# HDMI_CONNECTOR.net
KiCad netlist of a schematic drawn in Altium Designer
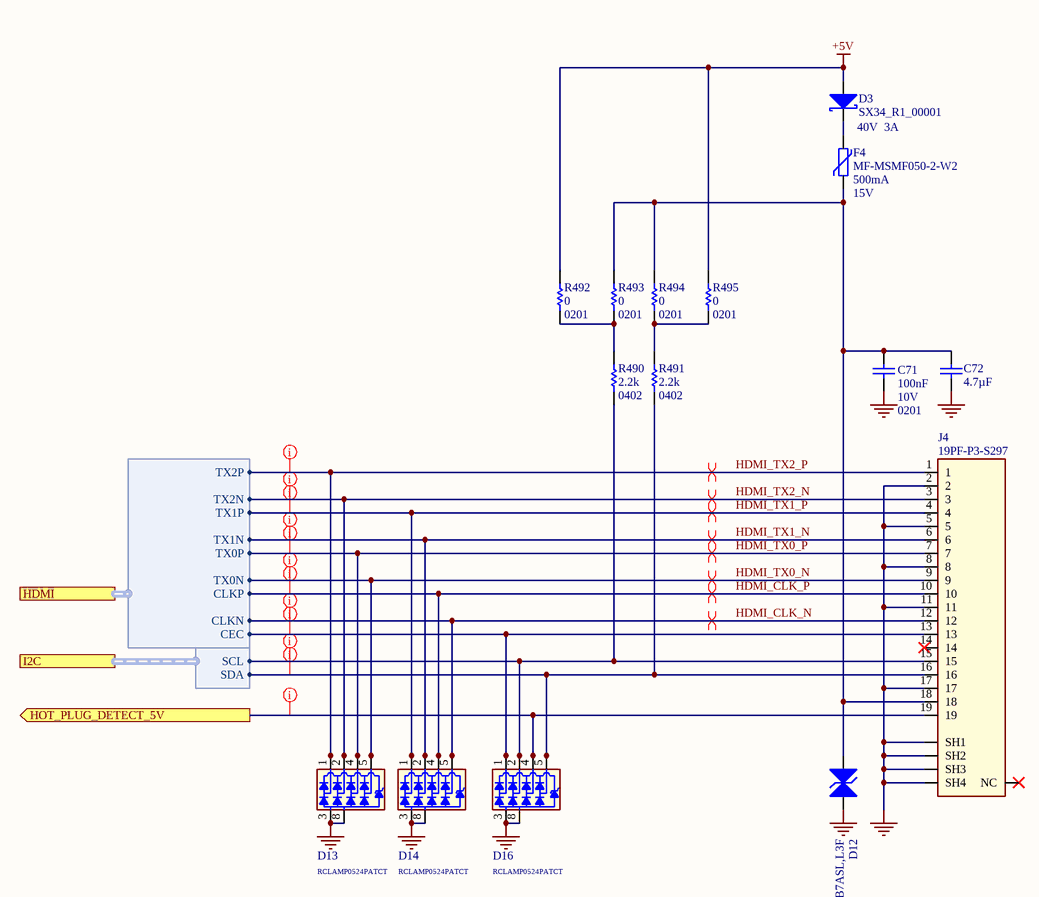
[diagram p0: HDMI_CONNECTOR.SchDoc]

(export (version "E")
  (design (tool "Eeschema 10.0.6"))
  (components
    (comp (ref "C71")
      (value "100nF")
      (footprint "CAP-0201")
      (description "CAP CHIP 0201 100nF 10% 10V X5R")
      (fields
        (field (name "PART NUMBER") "CL03A104KP3NNNC")
        (field (name "MANUFACTURER") "Samsung Electro-Mechanics")
        (field (name "VOLTAGE") "10V")
        (field (name "CASE CODE (IMPERIAL)") "0201")
      )
      (libsource (lib "Clean") (part "CAP"))
    )
    (comp (ref "C72")
      (value "4.7µF")
      (footprint "CAP-0402")
      (description "CAP CHIP 0402 4.7uF 20% 6V3 X5R")
      (fields (field (name "MANUFACTURER") "Hottech") (field (name "PART NUMBER") "C1005A475M6R3NT"))
      (libsource (lib "Clean") (part "CAP"))
    )
    (comp (ref "D3")
      (value "SX34_R1_00001")
      (footprint "SMA DO214AC")
      (description "DIODE SCHOTTKY SMD 3A 40V SMA DO214AC")
      (fields
        (field (name "PART NUMBER") "SX34-AU_R1_000A1")
        (field (name "MANUFACTURER") "Panjit")
        (field (name "MAX REVERSE VOLTAGE (DC)") "40V")
        (field (name "FORWARD CURRENT") "3A")
      )
      (libsource (lib "Clean") (part "Diode Schottky"))
    )
    (comp (ref "D12")
      (value "DF2B7ASL,L3F")
      (footprint "DF2B7ASL,L3F")
      (description "TVS BIDIRECTIONAL SMD Vr 5.5V, Vbr min 5.8V, 0.62x0.32mm")
      (fields (field (name "MANUFACTURER") "TOSHIBA"))
      (libsource (lib "Clean") (part "Diode TVS"))
    )
    (comp (ref "D13")
      (value "RCLAMP0524PATCT")
      (footprint "SLP2510P8")
      (description "TVS UNIDIRECTIONAL 4CH 0.8pF 5V SLP2510P8 10-pin 2.5x1.0x0.58mm")
      (fields (field (name "MANUFACTURER") "SEMTECH"))
      (libsource (lib "Clean") (part "RCLAMP0524PATCT"))
    )
    (comp (ref "D14")
      (value "RCLAMP0524PATCT")
      (footprint "SLP2510P8")
      (description "TVS UNIDIRECTIONAL 4CH 0.8pF 5V SLP2510P8 10-pin 2.5x1.0x0.58mm")
      (fields (field (name "MANUFACTURER") "SEMTECH"))
      (libsource (lib "Clean") (part "RCLAMP0524PATCT"))
    )
    (comp (ref "D16")
      (value "RCLAMP0524PATCT")
      (footprint "SLP2510P8")
      (description "TVS UNIDIRECTIONAL 4CH 0.8pF 5V SLP2510P8 10-pin 2.5x1.0x0.58mm")
      (fields (field (name "MANUFACTURER") "SEMTECH"))
      (libsource (lib "Clean") (part "RCLAMP0524PATCT"))
    )
    (comp (ref "F4")
      (value "MF-MSMF050-2-W2")
      (footprint "1812")
      (description "PTC RESET FUSE 15V 500MA 1812 LOGO OO ARDUINO")
      (fields
        (field (name "HOLD CURRENT") "500mA")
        (field (name "OPERATING SUPPLY VOLTAGE") "15V")
        (field (name "MANUFACTURER") "Bourns")
      )
      (libsource (lib "Clean") (part "Symbol"))
    )
    (comp (ref "J4")
      (value "19PF-P3-S297")
      (footprint "19PF-P3-S297")
      (description "CONN HDMI RIGHT ANGLE FEMALE 19 POSITIONS 7.75x23.06x16.4mm signals pins lengths 2.3mm")
      (fields (field (name "MANUFACTURER") "Contact technology"))
      (libsource (lib "Clean") (part "19PF-P3-S297"))
    )
    (comp (ref "R490")
      (value "2.2k")
      (footprint "RES-0402")
      (description "RES CHIP 0402 2k2 1% 1/16W")
      (fields
        (field (name "CASE CODE (IMPERIAL)") "0402")
        (field (name "POWER") "62.5mW")
        (field (name "TOLERANCE") "1%")
      )
      (libsource (lib "Clean") (part "RES"))
    )
    (comp (ref "R491")
      (value "2.2k")
      (footprint "RES-0402")
      (description "RES CHIP 0402 2k2 1% 1/16W")
      (fields
        (field (name "CASE CODE (IMPERIAL)") "0402")
        (field (name "POWER") "62.5mW")
        (field (name "TOLERANCE") "1%")
      )
      (libsource (lib "Clean") (part "RES"))
    )
    (comp (ref "R492")
      (value "0")
      (footprint "RES-0201")
      (description "RES CHIP 0201 0R")
      (fields
        (field (name "MANUFACTURER") "Vishay")
        (field (name "CASE CODE (IMPERIAL)") "0201")
        (field (name "PART NUMBER") "CRCW02010000Z0ED")
      )
      (libsource (lib "Clean") (part "RES"))
    )
    (comp (ref "R493")
      (value "0")
      (footprint "RES-0201")
      (description "RES CHIP 0201 0R")
      (fields
        (field (name "MANUFACTURER") "Vishay")
        (field (name "CASE CODE (IMPERIAL)") "0201")
        (field (name "PART NUMBER") "CRCW02010000Z0ED")
      )
      (libsource (lib "Clean") (part "RES"))
    )
    (comp (ref "R494")
      (value "0")
      (footprint "RES-0201")
      (description "RES CHIP 0201 0R")
      (fields
        (field (name "MANUFACTURER") "Vishay")
        (field (name "CASE CODE (IMPERIAL)") "0201")
        (field (name "PART NUMBER") "CRCW02010000Z0ED")
      )
      (libsource (lib "Clean") (part "RES"))
    )
    (comp (ref "R495")
      (value "0")
      (footprint "RES-0201")
      (description "RES CHIP 0201 0R")
      (fields
        (field (name "MANUFACTURER") "Vishay")
        (field (name "CASE CODE (IMPERIAL)") "0201")
        (field (name "PART NUMBER") "CRCW02010000Z0ED")
      )
      (libsource (lib "Clean") (part "RES"))
    )
  )
  (nets
    (net (code "3") (name "+5V") (class "Default")
      (node (ref "D3") (pin "A") (pinfunction "A_A") (pintype "passive"))
      (node (ref "R492") (pin "2") (pinfunction "2_2") (pintype "passive"))
      (node (ref "R495") (pin "2") (pinfunction "2_2") (pintype "passive"))
    )
    (net (code "4") (name "/HDMI_CLK_N") (class "Default")
      (node (ref "D14") (pin "5") (pinfunction "5_5") (pintype "passive"))
      (node (ref "D14") (pin "6") (pinfunction "6_6") (pintype "passive"))
      (node (ref "J4") (pin "12") (pinfunction "12_12") (pintype "passive"))
    )
    (net (code "5") (name "/HDMI_CLK_P") (class "Default")
      (node (ref "D14") (pin "4") (pinfunction "4_4") (pintype "passive"))
      (node (ref "D14") (pin "7") (pinfunction "7_7") (pintype "passive"))
      (node (ref "J4") (pin "10") (pinfunction "10_10") (pintype "passive"))
    )
    (net (code "6") (name "/HDMI_TX0_N") (class "Default")
      (node (ref "D13") (pin "5") (pinfunction "5_5") (pintype "passive"))
      (node (ref "D13") (pin "6") (pinfunction "6_6") (pintype "passive"))
      (node (ref "J4") (pin "9") (pinfunction "9_9") (pintype "passive"))
    )
    (net (code "7") (name "/HDMI_TX0_P") (class "Default")
      (node (ref "D13") (pin "4") (pinfunction "4_4") (pintype "passive"))
      (node (ref "D13") (pin "7") (pinfunction "7_7") (pintype "passive"))
      (node (ref "J4") (pin "7") (pinfunction "7_7") (pintype "passive"))
    )
    (net (code "8") (name "/HDMI_TX1_N") (class "Default")
      (node (ref "D14") (pin "2") (pinfunction "2_2") (pintype "passive"))
      (node (ref "D14") (pin "9") (pinfunction "9_9") (pintype "passive"))
      (node (ref "J4") (pin "6") (pinfunction "6_6") (pintype "passive"))
    )
    (net (code "9") (name "/HDMI_TX1_P") (class "Default")
      (node (ref "D14") (pin "1") (pinfunction "1_1") (pintype "passive"))
      (node (ref "D14") (pin "10") (pinfunction "10_10") (pintype "passive"))
      (node (ref "J4") (pin "4") (pinfunction "4_4") (pintype "passive"))
    )
    (net (code "10") (name "/HDMI_TX2_N") (class "Default")
      (node (ref "D13") (pin "2") (pinfunction "2_2") (pintype "passive"))
      (node (ref "D13") (pin "9") (pinfunction "9_9") (pintype "passive"))
      (node (ref "J4") (pin "3") (pinfunction "3_3") (pintype "passive"))
    )
    (net (code "11") (name "/HDMI_TX2_P") (class "Default")
      (node (ref "D13") (pin "1") (pinfunction "1_1") (pintype "passive"))
      (node (ref "D13") (pin "10") (pinfunction "10_10") (pintype "passive"))
      (node (ref "J4") (pin "1") (pinfunction "1_1") (pintype "passive"))
    )
    (net (code "13") (name "/HOT_PLUG_DETECT_5V") (class "Default")
      (node (ref "D16") (pin "4") (pinfunction "4_4") (pintype "passive"))
      (node (ref "D16") (pin "7") (pinfunction "7_7") (pintype "passive"))
      (node (ref "J4") (pin "19") (pinfunction "19_19") (pintype "passive"))
    )
    (net (code "15") (name "GND") (class "Default")
      (node (ref "C71") (pin "1") (pinfunction "1_1") (pintype "passive"))
      (node (ref "C72") (pin "1") (pinfunction "1_1") (pintype "passive"))
      (node (ref "D12") (pin "1") (pinfunction "A1_1") (pintype "passive"))
      (node (ref "D13") (pin "3") (pinfunction "3_3") (pintype "passive"))
      (node (ref "D13") (pin "8") (pinfunction "8_8") (pintype "passive"))
      (node (ref "D14") (pin "3") (pinfunction "3_3") (pintype "passive"))
      (node (ref "D14") (pin "8") (pinfunction "8_8") (pintype "passive"))
      (node (ref "D16") (pin "3") (pinfunction "3_3") (pintype "passive"))
      (node (ref "D16") (pin "8") (pinfunction "8_8") (pintype "passive"))
      (node (ref "J4") (pin "11") (pinfunction "11_11") (pintype "passive"))
      (node (ref "J4") (pin "17") (pinfunction "17_17") (pintype "passive"))
      (node (ref "J4") (pin "2") (pinfunction "2_2") (pintype "passive"))
      (node (ref "J4") (pin "5") (pinfunction "5_5") (pintype "passive"))
      (node (ref "J4") (pin "8") (pinfunction "8_8") (pintype "passive"))
      (node (ref "J4") (pin "SH1") (pinfunction "SH1_SH1") (pintype "passive"))
      (node (ref "J4") (pin "SH2") (pinfunction "SH2_SH2") (pintype "passive"))
      (node (ref "J4") (pin "SH3") (pinfunction "SH3_SH3") (pintype "passive"))
      (node (ref "J4") (pin "SH4") (pinfunction "SH4_SH4") (pintype "passive"))
    )
    (net (code "16") (name "Net-(D3-PadC)") (class "Default")
      (node (ref "D3") (pin "C") (pinfunction "C_C") (pintype "passive"))
      (node (ref "F4") (pin "2") (pinfunction "2_2") (pintype "passive"))
    )
    (net (code "17") (name "Net-(D12-A2)") (class "Default")
      (node (ref "C71") (pin "2") (pinfunction "2_2") (pintype "passive"))
      (node (ref "C72") (pin "2") (pinfunction "2_2") (pintype "passive"))
      (node (ref "D12") (pin "2") (pinfunction "A2_2") (pintype "passive"))
      (node (ref "F4") (pin "1") (pinfunction "1_1") (pintype "passive"))
      (node (ref "J4") (pin "18") (pinfunction "18_18") (pintype "passive"))
      (node (ref "R493") (pin "2") (pinfunction "2_2") (pintype "passive"))
      (node (ref "R494") (pin "2") (pinfunction "2_2") (pintype "passive"))
    )
    (net (code "18") (name "Net-(D16-Pad1)") (class "Default")
      (node (ref "D16") (pin "1") (pinfunction "1_1") (pintype "passive"))
      (node (ref "D16") (pin "10") (pinfunction "10_10") (pintype "passive"))
      (node (ref "J4") (pin "13") (pinfunction "13_13") (pintype "passive"))
    )
    (net (code "19") (name "Net-(D16-Pad2)") (class "Default")
      (node (ref "D16") (pin "2") (pinfunction "2_2") (pintype "passive"))
      (node (ref "D16") (pin "9") (pinfunction "9_9") (pintype "passive"))
      (node (ref "J4") (pin "15") (pinfunction "15_15") (pintype "passive"))
      (node (ref "R490") (pin "2") (pinfunction "2_2") (pintype "passive"))
    )
    (net (code "20") (name "Net-(D16-Pad5)") (class "Default")
      (node (ref "D16") (pin "5") (pinfunction "5_5") (pintype "passive"))
      (node (ref "D16") (pin "6") (pinfunction "6_6") (pintype "passive"))
      (node (ref "J4") (pin "16") (pinfunction "16_16") (pintype "passive"))
      (node (ref "R491") (pin "2") (pinfunction "2_2") (pintype "passive"))
    )
    (net (code "21") (name "Net-(R490-Pad1)") (class "Default")
      (node (ref "R490") (pin "1") (pinfunction "1_1") (pintype "passive"))
      (node (ref "R492") (pin "1") (pinfunction "1_1") (pintype "passive"))
      (node (ref "R493") (pin "1") (pinfunction "1_1") (pintype "passive"))
    )
    (net (code "22") (name "Net-(R491-Pad1)") (class "Default")
      (node (ref "R491") (pin "1") (pinfunction "1_1") (pintype "passive"))
      (node (ref "R494") (pin "1") (pinfunction "1_1") (pintype "passive"))
      (node (ref "R495") (pin "1") (pinfunction "1_1") (pintype "passive"))
    )
    (net (code "23") (name "unconnected-(J4-Pad14)") (class "Default")
      (node (ref "J4") (pin "14") (pinfunction "14_14") (pintype "passive+no_connect"))
    )
    (net (code "24") (name "unconnected-(J4-PadNC)") (class "Default")
      (node (ref "J4") (pin "NC") (pinfunction "NC_NC") (pintype "passive+no_connect"))
    )
  )
)
